# UpTo11_MotherBoard.net
KiCad netlist of a schematic drawn in EAGLE
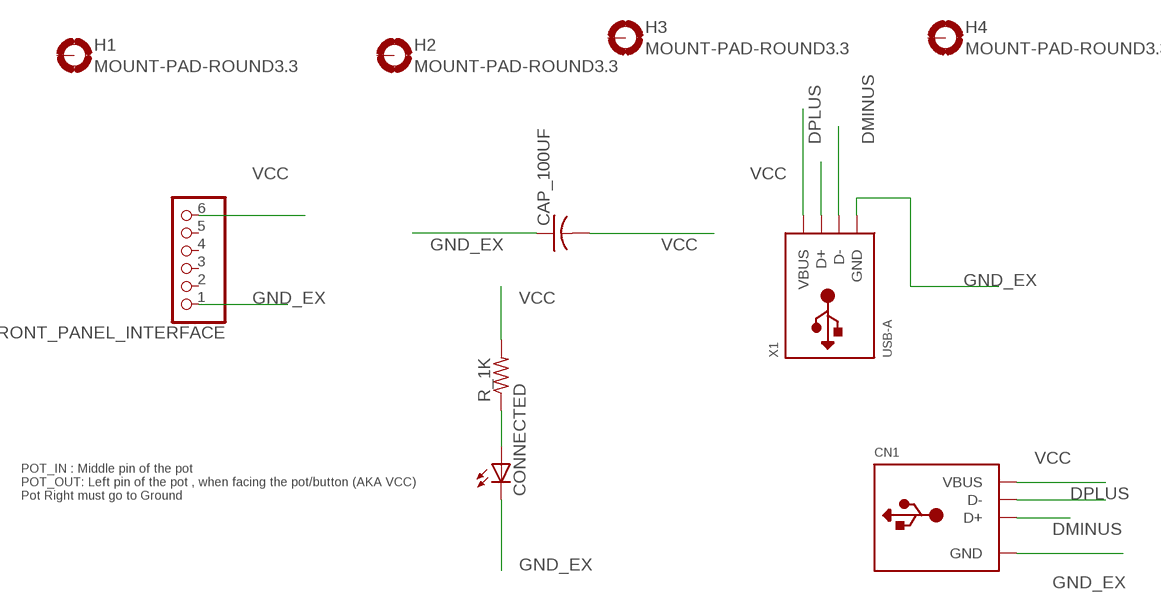
[diagram p0: schematic, sheet 1]

(export (version "E")
  (design (tool "Eeschema 10.0.6"))
  (components
    (comp (ref "CAP_100UF")
      (value "C-US025-030X050")
      (footprint "eagle-import:C025-030X050")
      (libsource (lib "eagle-import") (part "C-US025-030X050"))
    )
    (comp (ref "CN1")
      (value "USB_TYPEAPTHFML")
      (footprint "eagle-import:USB_HOST-PTH")
      (libsource (lib "eagle-import") (part "USB_TYPEAPTHFML"))
    )
    (comp (ref "CONNECTED")
      (value "LEDSMT1206")
      (footprint "eagle-import:1206")
      (libsource (lib "eagle-import") (part "LEDSMT1206"))
    )
    (comp (ref "FRONT_PANEL_INTERFACE")
      (value "PINHD-1X6")
      (footprint "eagle-import:1X06")
      (libsource (lib "eagle-import") (part "PINHD-1X6"))
    )
    (comp (ref "H1")
      (value "MOUNT-PAD-ROUND3.3")
      (footprint "eagle-import:3,3-PAD")
      (libsource (lib "eagle-import") (part "MOUNT-PAD-ROUND3.3"))
    )
    (comp (ref "H2")
      (value "MOUNT-PAD-ROUND3.3")
      (footprint "eagle-import:3,3-PAD")
      (libsource (lib "eagle-import") (part "MOUNT-PAD-ROUND3.3"))
    )
    (comp (ref "H3")
      (value "MOUNT-PAD-ROUND3.3")
      (footprint "eagle-import:3,3-PAD")
      (libsource (lib "eagle-import") (part "MOUNT-PAD-ROUND3.3"))
    )
    (comp (ref "H4")
      (value "MOUNT-PAD-ROUND3.3")
      (footprint "eagle-import:3,3-PAD")
      (libsource (lib "eagle-import") (part "MOUNT-PAD-ROUND3.3"))
    )
    (comp (ref "R_1K")
      (value "R-US_R1206")
      (footprint "eagle-import:R1206")
      (libsource (lib "eagle-import") (part "R-US_R1206"))
    )
    (comp (ref "X1")
      (value "USB-A")
      (footprint "eagle-import:MOLEX_480371000")
      (libsource (lib "eagle-import") (part "USB-A"))
    )
  )
  (nets
    (net (code "1") (name "/DMINUS") (class "Default")
      (node (ref "CN1") (pin "D+") (pinfunction "D+_D+") (pintype "bidirectional"))
      (node (ref "X1") (pin "2") (pinfunction "D-_2") (pintype "bidirectional"))
    )
    (net (code "2") (name "/DPLUS") (class "Default")
      (node (ref "CN1") (pin "D-") (pinfunction "D-_D-") (pintype "bidirectional"))
      (node (ref "X1") (pin "3") (pinfunction "D+_3") (pintype "bidirectional"))
    )
    (net (code "3") (name "/GND_EX") (class "Default")
      (node (ref "CAP_100UF") (pin "1") (pinfunction "1_1") (pintype "passive"))
      (node (ref "CN1") (pin "GND") (pinfunction "GND_GND") (pintype "power_in"))
      (node (ref "CONNECTED") (pin "C") (pinfunction "C_C") (pintype "passive"))
      (node (ref "FRONT_PANEL_INTERFACE") (pin "1") (pinfunction "1_1") (pintype "passive"))
      (node (ref "X1") (pin "4") (pinfunction "GND_4") (pintype "power_in"))
    )
    (net (code "4") (name "/VCC") (class "Default")
      (node (ref "CAP_100UF") (pin "2") (pinfunction "2_2") (pintype "passive"))
      (node (ref "CN1") (pin "VBUS") (pinfunction "VBUS_VBUS") (pintype "power_in"))
      (node (ref "FRONT_PANEL_INTERFACE") (pin "6") (pinfunction "6_6") (pintype "passive"))
      (node (ref "R_1K") (pin "2") (pinfunction "2_2") (pintype "passive"))
      (node (ref "X1") (pin "1") (pinfunction "VBUS_1") (pintype "power_in"))
    )
    (net (code "5") (name "Net-(CONNECTED-PadA)") (class "Default")
      (node (ref "CONNECTED") (pin "A") (pinfunction "A_A") (pintype "passive"))
      (node (ref "R_1K") (pin "1") (pinfunction "1_1") (pintype "passive"))
    )
    (net (code "6") (name "unconnected-(FRONT_PANEL_INTERFACE-Pad2)") (class "Default")
      (node (ref "FRONT_PANEL_INTERFACE") (pin "2") (pinfunction "2_2") (pintype "passive"))
    )
    (net (code "7") (name "unconnected-(FRONT_PANEL_INTERFACE-Pad3)") (class "Default")
      (node (ref "FRONT_PANEL_INTERFACE") (pin "3") (pinfunction "3_3") (pintype "passive"))
    )
    (net (code "8") (name "unconnected-(FRONT_PANEL_INTERFACE-Pad4)") (class "Default")
      (node (ref "FRONT_PANEL_INTERFACE") (pin "4") (pinfunction "4_4") (pintype "passive"))
    )
    (net (code "9") (name "unconnected-(FRONT_PANEL_INTERFACE-Pad5)") (class "Default")
      (node (ref "FRONT_PANEL_INTERFACE") (pin "5") (pinfunction "5_5") (pintype "passive"))
    )
    (net (code "10") (name "unconnected-(H1-MOUNT-PadB3,3)") (class "Default")
      (node (ref "H1") (pin "B3,3") (pinfunction "MOUNT_B3,3") (pintype "passive"))
    )
    (net (code "11") (name "unconnected-(H2-MOUNT-PadB3,3)") (class "Default")
      (node (ref "H2") (pin "B3,3") (pinfunction "MOUNT_B3,3") (pintype "passive"))
    )
    (net (code "12") (name "unconnected-(H3-MOUNT-PadB3,3)") (class "Default")
      (node (ref "H3") (pin "B3,3") (pinfunction "MOUNT_B3,3") (pintype "passive"))
    )
    (net (code "13") (name "unconnected-(H4-MOUNT-PadB3,3)") (class "Default")
      (node (ref "H4") (pin "B3,3") (pinfunction "MOUNT_B3,3") (pintype "passive"))
    )
  )
)
